# GBZP-no-mcu.net
KiCad netlist of a schematic drawn in EAGLE
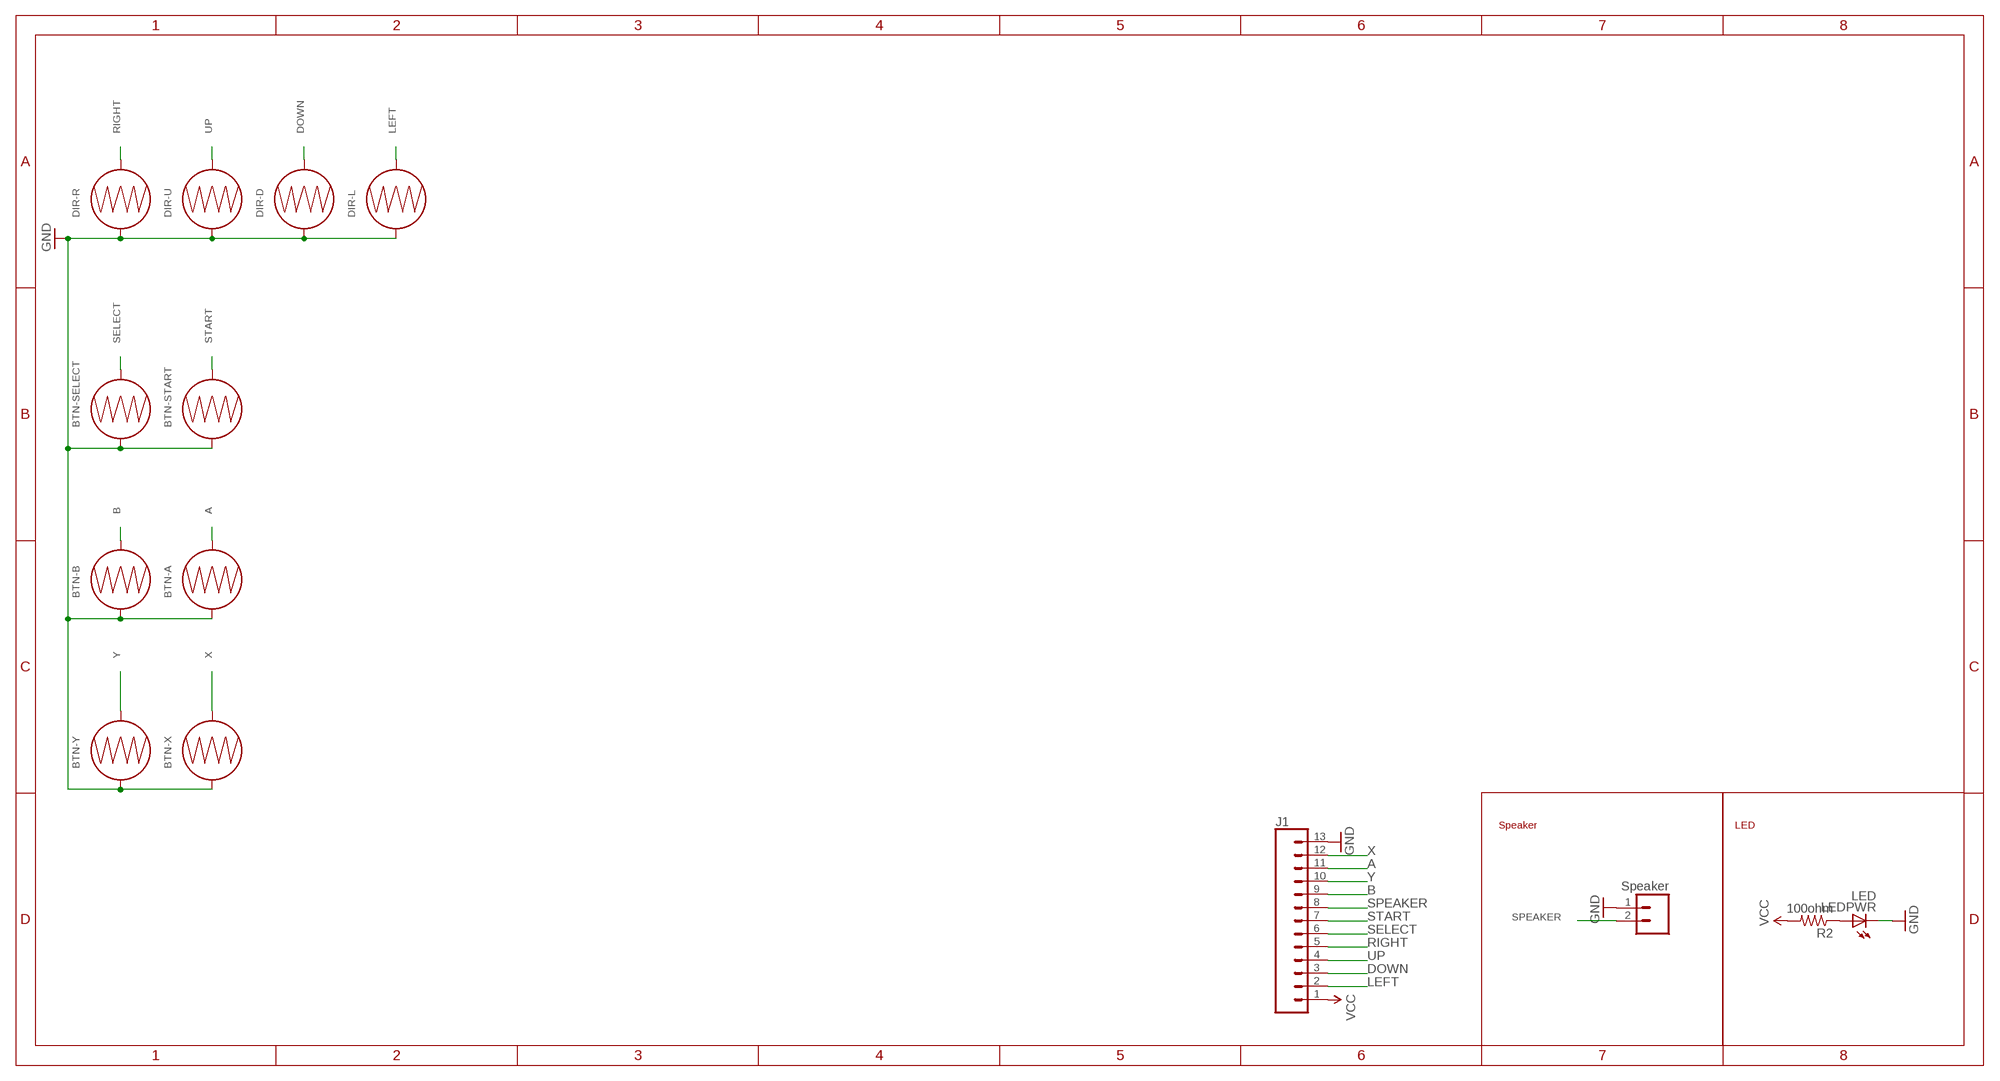
[diagram p0: schematic, sheet 1]

(export (version "E")
  (design (tool "Eeschema 10.0.6"))
  (components
    (comp (ref "BTN-A")
      (value "BUTTON-CONDUCTIVESMD")
      (footprint "eagle-import:BUTTON-CONDUCTIVE")
      (libsource (lib "eagle-import") (part "BUTTON-CONDUCTIVESMD"))
    )
    (comp (ref "BTN-B")
      (value "BUTTON-CONDUCTIVESMD")
      (footprint "eagle-import:BUTTON-CONDUCTIVE")
      (libsource (lib "eagle-import") (part "BUTTON-CONDUCTIVESMD"))
    )
    (comp (ref "BTN-SELECT")
      (value "BUTTON-CONDUCTIVESMD")
      (footprint "eagle-import:BUTTON-CONDUCTIVE")
      (libsource (lib "eagle-import") (part "BUTTON-CONDUCTIVESMD"))
    )
    (comp (ref "BTN-START")
      (value "BUTTON-CONDUCTIVESMD")
      (footprint "eagle-import:BUTTON-CONDUCTIVE")
      (libsource (lib "eagle-import") (part "BUTTON-CONDUCTIVESMD"))
    )
    (comp (ref "BTN-X")
      (value "BUTTON-CONDUCTIVESMD")
      (footprint "eagle-import:BUTTON-CONDUCTIVE")
      (libsource (lib "eagle-import") (part "BUTTON-CONDUCTIVESMD"))
    )
    (comp (ref "BTN-Y")
      (value "BUTTON-CONDUCTIVESMD")
      (footprint "eagle-import:BUTTON-CONDUCTIVE")
      (libsource (lib "eagle-import") (part "BUTTON-CONDUCTIVESMD"))
    )
    (comp (ref "DIR-D")
      (value "BUTTON-CONDUCTIVESMD")
      (footprint "eagle-import:BUTTON-CONDUCTIVE")
      (libsource (lib "eagle-import") (part "BUTTON-CONDUCTIVESMD"))
    )
    (comp (ref "DIR-L")
      (value "BUTTON-CONDUCTIVESMD")
      (footprint "eagle-import:BUTTON-CONDUCTIVE")
      (libsource (lib "eagle-import") (part "BUTTON-CONDUCTIVESMD"))
    )
    (comp (ref "DIR-R")
      (value "BUTTON-CONDUCTIVESMD")
      (footprint "eagle-import:BUTTON-CONDUCTIVE")
      (libsource (lib "eagle-import") (part "BUTTON-CONDUCTIVESMD"))
    )
    (comp (ref "DIR-U")
      (value "BUTTON-CONDUCTIVESMD")
      (footprint "eagle-import:BUTTON-CONDUCTIVE")
      (libsource (lib "eagle-import") (part "BUTTON-CONDUCTIVESMD"))
    )
    (comp (ref "J1")
      (value "CONN_13")
      (footprint "eagle-import:1X13")
      (libsource (lib "eagle-import") (part "CONN_13"))
    )
    (comp (ref "JP2")
      (value "Speaker")
      (footprint "eagle-import:1X02_NO_SILK")
      (libsource (lib "eagle-import") (part "M021X02_NO_SILK"))
    )
    (comp (ref "LEDPWR")
      (value "LED")
      (footprint "eagle-import:CHIPLED_0805")
      (libsource (lib "eagle-import") (part "LEDCHIPLED_0805"))
    )
    (comp (ref "R2")
      (value "100ohm")
      (footprint "eagle-import:R0805")
      (libsource (lib "eagle-import") (part "R-US_R0805"))
    )
  )
  (nets
    (net (code "1") (name "/A") (class "Default")
      (node (ref "BTN-A") (pin "2") (pinfunction "2_2") (pintype "passive"))
      (node (ref "J1") (pin "11") (pinfunction "11_11") (pintype "passive"))
    )
    (net (code "2") (name "/B") (class "Default")
      (node (ref "BTN-B") (pin "2") (pinfunction "2_2") (pintype "passive"))
      (node (ref "J1") (pin "9") (pinfunction "9_9") (pintype "passive"))
    )
    (net (code "3") (name "/DOWN") (class "Default")
      (node (ref "DIR-D") (pin "2") (pinfunction "2_2") (pintype "passive"))
      (node (ref "J1") (pin "3") (pinfunction "3_3") (pintype "passive"))
    )
    (net (code "4") (name "/LEFT") (class "Default")
      (node (ref "DIR-L") (pin "2") (pinfunction "2_2") (pintype "passive"))
      (node (ref "J1") (pin "2") (pinfunction "2_2") (pintype "passive"))
    )
    (net (code "5") (name "/RIGHT") (class "Default")
      (node (ref "DIR-R") (pin "2") (pinfunction "2_2") (pintype "passive"))
      (node (ref "J1") (pin "5") (pinfunction "5_5") (pintype "passive"))
    )
    (net (code "6") (name "/SELECT") (class "Default")
      (node (ref "BTN-SELECT") (pin "2") (pinfunction "2_2") (pintype "passive"))
      (node (ref "J1") (pin "6") (pinfunction "6_6") (pintype "passive"))
    )
    (net (code "7") (name "/SPEAKER") (class "Default")
      (node (ref "J1") (pin "8") (pinfunction "8_8") (pintype "passive"))
      (node (ref "JP2") (pin "2") (pinfunction "2_2") (pintype "passive"))
    )
    (net (code "8") (name "/START") (class "Default")
      (node (ref "BTN-START") (pin "2") (pinfunction "2_2") (pintype "passive"))
      (node (ref "J1") (pin "7") (pinfunction "7_7") (pintype "passive"))
    )
    (net (code "9") (name "/UP") (class "Default")
      (node (ref "DIR-U") (pin "2") (pinfunction "2_2") (pintype "passive"))
      (node (ref "J1") (pin "4") (pinfunction "4_4") (pintype "passive"))
    )
    (net (code "10") (name "/X") (class "Default")
      (node (ref "BTN-X") (pin "2") (pinfunction "2_2") (pintype "passive"))
      (node (ref "J1") (pin "12") (pinfunction "12_12") (pintype "passive"))
    )
    (net (code "11") (name "/Y") (class "Default")
      (node (ref "BTN-Y") (pin "2") (pinfunction "2_2") (pintype "passive"))
      (node (ref "J1") (pin "10") (pinfunction "10_10") (pintype "passive"))
    )
    (net (code "12") (name "GND") (class "Default")
      (node (ref "BTN-A") (pin "1") (pinfunction "1_1") (pintype "passive"))
      (node (ref "BTN-B") (pin "1") (pinfunction "1_1") (pintype "passive"))
      (node (ref "BTN-SELECT") (pin "1") (pinfunction "1_1") (pintype "passive"))
      (node (ref "BTN-START") (pin "1") (pinfunction "1_1") (pintype "passive"))
      (node (ref "BTN-X") (pin "1") (pinfunction "1_1") (pintype "passive"))
      (node (ref "BTN-Y") (pin "1") (pinfunction "1_1") (pintype "passive"))
      (node (ref "DIR-D") (pin "1") (pinfunction "1_1") (pintype "passive"))
      (node (ref "DIR-L") (pin "1") (pinfunction "1_1") (pintype "passive"))
      (node (ref "DIR-R") (pin "1") (pinfunction "1_1") (pintype "passive"))
      (node (ref "DIR-U") (pin "1") (pinfunction "1_1") (pintype "passive"))
      (node (ref "J1") (pin "13") (pinfunction "13_13") (pintype "passive"))
      (node (ref "JP2") (pin "1") (pinfunction "1_1") (pintype "passive"))
      (node (ref "LEDPWR") (pin "C") (pinfunction "C_C") (pintype "passive"))
    )
    (net (code "13") (name "Net-(LEDPWR-PadA)") (class "Default")
      (node (ref "LEDPWR") (pin "A") (pinfunction "A_A") (pintype "passive"))
      (node (ref "R2") (pin "1") (pinfunction "1_1") (pintype "passive"))
    )
    (net (code "14") (name "VCC") (class "Default")
      (node (ref "J1") (pin "1") (pinfunction "1_1") (pintype "passive"))
      (node (ref "R2") (pin "2") (pinfunction "2_2") (pintype "passive"))
    )
  )
)
